# Daughter_Board.net
KiCad netlist of a schematic drawn in Altium Designer
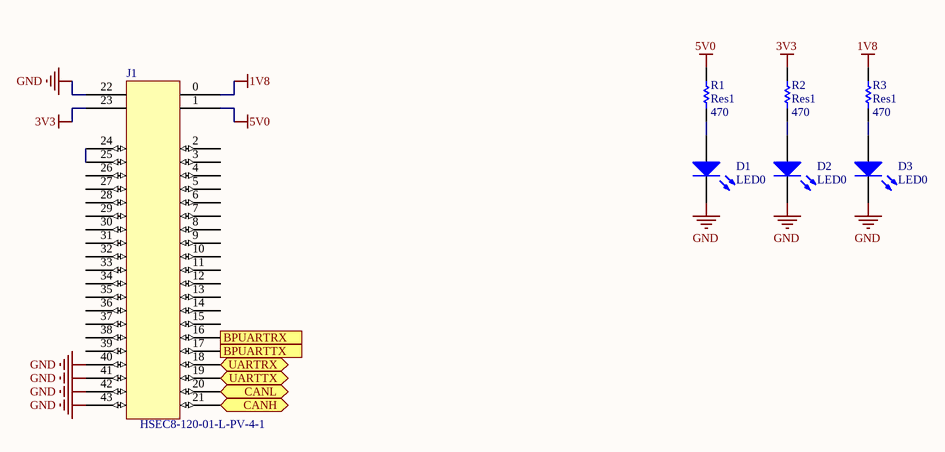
[diagram p0: Daughter Board.SchDoc]

(export (version "E")
  (design (tool "Eeschema 10.0.6"))
  (components
    (comp (ref "D1")
      (value "LED0")
      (footprint "1608[0603]")
      (fields (field (name "PUBLISHER") "Altium Limited"))
      (libsource (lib "Miscellaneous Devices") (part "LED0"))
    )
    (comp (ref "D2")
      (value "LED0")
      (footprint "1608[0603]")
      (fields (field (name "PUBLISHER") "Altium Limited"))
      (libsource (lib "Miscellaneous Devices") (part "LED0"))
    )
    (comp (ref "D3")
      (value "LED0")
      (footprint "1608[0603]")
      (fields (field (name "PUBLISHER") "Altium Limited"))
      (libsource (lib "Miscellaneous Devices") (part "LED0"))
    )
    (comp (ref "J1")
      (value "HSEC8-120-01-L-PV-4-1")
      (footprint "HSEC8-120-01-L-PV-4-1 Gold Fingers")
      (libsource (lib "Edge Connector") (part "HSEC8-120-01-L-PV-4-1"))
    )
    (comp (ref "R1")
      (value "Res1")
      (footprint "1608[0603]")
      (description "Resistor")
      (fields (field (name "ALTIUM_VALUE") "470") (field (name "PUBLISHER") "Altium Limited"))
      (libsource (lib "Miscellaneous Devices") (part "Res1"))
    )
    (comp (ref "R2")
      (value "Res1")
      (footprint "1608[0603]")
      (description "Resistor")
      (fields (field (name "ALTIUM_VALUE") "470") (field (name "PUBLISHER") "Altium Limited"))
      (libsource (lib "Miscellaneous Devices") (part "Res1"))
    )
    (comp (ref "R3")
      (value "Res1")
      (footprint "1608[0603]")
      (description "Resistor")
      (fields (field (name "ALTIUM_VALUE") "470") (field (name "PUBLISHER") "Altium Limited"))
      (libsource (lib "Miscellaneous Devices") (part "Res1"))
    )
  )
  (nets
    (net (code "1") (name "/BPUARTRX") (class "Default")
      (node (ref "J1") (pin "16") (pinfunction "0_16") (pintype "bidirectional"))
    )
    (net (code "2") (name "/BPUARTTX") (class "Default")
      (node (ref "J1") (pin "17") (pinfunction "0_17") (pintype "bidirectional"))
    )
    (net (code "3") (name "/CANH") (class "Default")
      (node (ref "J1") (pin "21") (pinfunction "0_21") (pintype "bidirectional"))
    )
    (net (code "4") (name "/CANL") (class "Default")
      (node (ref "J1") (pin "20") (pinfunction "0_20") (pintype "bidirectional"))
    )
    (net (code "5") (name "/UARTRX") (class "Default")
      (node (ref "J1") (pin "18") (pinfunction "0_18") (pintype "bidirectional"))
    )
    (net (code "6") (name "/UARTTX") (class "Default")
      (node (ref "J1") (pin "19") (pinfunction "0_19") (pintype "bidirectional"))
    )
    (net (code "7") (name "1V8") (class "Default")
      (node (ref "J1") (pin "0") (pinfunction "0_0") (pintype "power_in"))
      (node (ref "R3") (pin "2") (pinfunction "2_2") (pintype "passive"))
    )
    (net (code "8") (name "3V3") (class "Default")
      (node (ref "J1") (pin "23") (pinfunction "23_23") (pintype "power_in"))
      (node (ref "R2") (pin "2") (pinfunction "2_2") (pintype "passive"))
    )
    (net (code "9") (name "5V0") (class "Default")
      (node (ref "J1") (pin "1") (pinfunction "0_1") (pintype "power_in"))
      (node (ref "R1") (pin "2") (pinfunction "2_2") (pintype "passive"))
    )
    (net (code "10") (name "GND") (class "Default")
      (node (ref "D1") (pin "2") (pinfunction "K_2") (pintype "passive"))
      (node (ref "D2") (pin "2") (pinfunction "K_2") (pintype "passive"))
      (node (ref "D3") (pin "2") (pinfunction "K_2") (pintype "passive"))
      (node (ref "J1") (pin "22") (pinfunction "0_22") (pintype "power_in"))
      (node (ref "J1") (pin "40") (pinfunction "40_40") (pintype "bidirectional"))
      (node (ref "J1") (pin "41") (pinfunction "41_41") (pintype "bidirectional"))
      (node (ref "J1") (pin "42") (pinfunction "42_42") (pintype "bidirectional"))
      (node (ref "J1") (pin "43") (pinfunction "43_43") (pintype "bidirectional"))
    )
    (net (code "11") (name "Net-(D1-A)") (class "Default")
      (node (ref "D1") (pin "1") (pinfunction "A_1") (pintype "passive"))
      (node (ref "R1") (pin "1") (pinfunction "1_1") (pintype "passive"))
    )
    (net (code "12") (name "Net-(D2-A)") (class "Default")
      (node (ref "D2") (pin "1") (pinfunction "A_1") (pintype "passive"))
      (node (ref "R2") (pin "1") (pinfunction "1_1") (pintype "passive"))
    )
    (net (code "13") (name "Net-(D3-A)") (class "Default")
      (node (ref "D3") (pin "1") (pinfunction "A_1") (pintype "passive"))
      (node (ref "R3") (pin "1") (pinfunction "1_1") (pintype "passive"))
    )
    (net (code "14") (name "Net-(J1-Pad24)") (class "Default")
      (node (ref "J1") (pin "24") (pinfunction "24_24") (pintype "bidirectional"))
      (node (ref "J1") (pin "25") (pinfunction "25_25") (pintype "bidirectional"))
    )
    (net (code "15") (name "unconnected-(J1-0-Pad2)") (class "Default")
      (node (ref "J1") (pin "2") (pinfunction "0_2") (pintype "bidirectional"))
    )
    (net (code "16") (name "unconnected-(J1-0-Pad3)") (class "Default")
      (node (ref "J1") (pin "3") (pinfunction "0_3") (pintype "bidirectional"))
    )
    (net (code "17") (name "unconnected-(J1-0-Pad4)") (class "Default")
      (node (ref "J1") (pin "4") (pinfunction "0_4") (pintype "bidirectional"))
    )
    (net (code "18") (name "unconnected-(J1-0-Pad5)") (class "Default")
      (node (ref "J1") (pin "5") (pinfunction "0_5") (pintype "bidirectional"))
    )
    (net (code "19") (name "unconnected-(J1-0-Pad6)") (class "Default")
      (node (ref "J1") (pin "6") (pinfunction "0_6") (pintype "bidirectional"))
    )
    (net (code "20") (name "unconnected-(J1-0-Pad7)") (class "Default")
      (node (ref "J1") (pin "7") (pinfunction "0_7") (pintype "bidirectional"))
    )
    (net (code "21") (name "unconnected-(J1-0-Pad8)") (class "Default")
      (node (ref "J1") (pin "8") (pinfunction "0_8") (pintype "bidirectional"))
    )
    (net (code "22") (name "unconnected-(J1-0-Pad9)") (class "Default")
      (node (ref "J1") (pin "9") (pinfunction "0_9") (pintype "bidirectional"))
    )
    (net (code "23") (name "unconnected-(J1-0-Pad10)") (class "Default")
      (node (ref "J1") (pin "10") (pinfunction "0_10") (pintype "bidirectional"))
    )
    (net (code "24") (name "unconnected-(J1-0-Pad11)") (class "Default")
      (node (ref "J1") (pin "11") (pinfunction "0_11") (pintype "bidirectional"))
    )
    (net (code "25") (name "unconnected-(J1-0-Pad12)") (class "Default")
      (node (ref "J1") (pin "12") (pinfunction "0_12") (pintype "bidirectional"))
    )
    (net (code "26") (name "unconnected-(J1-0-Pad13)") (class "Default")
      (node (ref "J1") (pin "13") (pinfunction "0_13") (pintype "bidirectional"))
    )
    (net (code "27") (name "unconnected-(J1-0-Pad14)") (class "Default")
      (node (ref "J1") (pin "14") (pinfunction "0_14") (pintype "bidirectional"))
    )
    (net (code "28") (name "unconnected-(J1-0-Pad15)") (class "Default")
      (node (ref "J1") (pin "15") (pinfunction "0_15") (pintype "bidirectional"))
    )
    (net (code "29") (name "unconnected-(J1-Pad26)") (class "Default")
      (node (ref "J1") (pin "26") (pinfunction "26_26") (pintype "bidirectional"))
    )
    (net (code "30") (name "unconnected-(J1-Pad27)") (class "Default")
      (node (ref "J1") (pin "27") (pinfunction "27_27") (pintype "bidirectional"))
    )
    (net (code "31") (name "unconnected-(J1-Pad28)") (class "Default")
      (node (ref "J1") (pin "28") (pinfunction "28_28") (pintype "bidirectional"))
    )
    (net (code "32") (name "unconnected-(J1-Pad29)") (class "Default")
      (node (ref "J1") (pin "29") (pinfunction "29_29") (pintype "bidirectional"))
    )
    (net (code "33") (name "unconnected-(J1-Pad30)") (class "Default")
      (node (ref "J1") (pin "30") (pinfunction "30_30") (pintype "bidirectional"))
    )
    (net (code "34") (name "unconnected-(J1-Pad31)") (class "Default")
      (node (ref "J1") (pin "31") (pinfunction "31_31") (pintype "bidirectional"))
    )
    (net (code "35") (name "unconnected-(J1-Pad32)") (class "Default")
      (node (ref "J1") (pin "32") (pinfunction "32_32") (pintype "bidirectional"))
    )
    (net (code "36") (name "unconnected-(J1-Pad33)") (class "Default")
      (node (ref "J1") (pin "33") (pinfunction "33_33") (pintype "bidirectional"))
    )
    (net (code "37") (name "unconnected-(J1-Pad34)") (class "Default")
      (node (ref "J1") (pin "34") (pinfunction "34_34") (pintype "bidirectional"))
    )
    (net (code "38") (name "unconnected-(J1-Pad35)") (class "Default")
      (node (ref "J1") (pin "35") (pinfunction "35_35") (pintype "bidirectional"))
    )
    (net (code "39") (name "unconnected-(J1-Pad36)") (class "Default")
      (node (ref "J1") (pin "36") (pinfunction "36_36") (pintype "bidirectional"))
    )
    (net (code "40") (name "unconnected-(J1-Pad37)") (class "Default")
      (node (ref "J1") (pin "37") (pinfunction "37_37") (pintype "bidirectional"))
    )
    (net (code "41") (name "unconnected-(J1-Pad38)") (class "Default")
      (node (ref "J1") (pin "38") (pinfunction "38_38") (pintype "bidirectional"))
    )
    (net (code "42") (name "unconnected-(J1-Pad39)") (class "Default")
      (node (ref "J1") (pin "39") (pinfunction "39_39") (pintype "bidirectional"))
    )
  )
)
